# LCD_RGB.net
KiCad netlist of a schematic drawn in Altium Designer
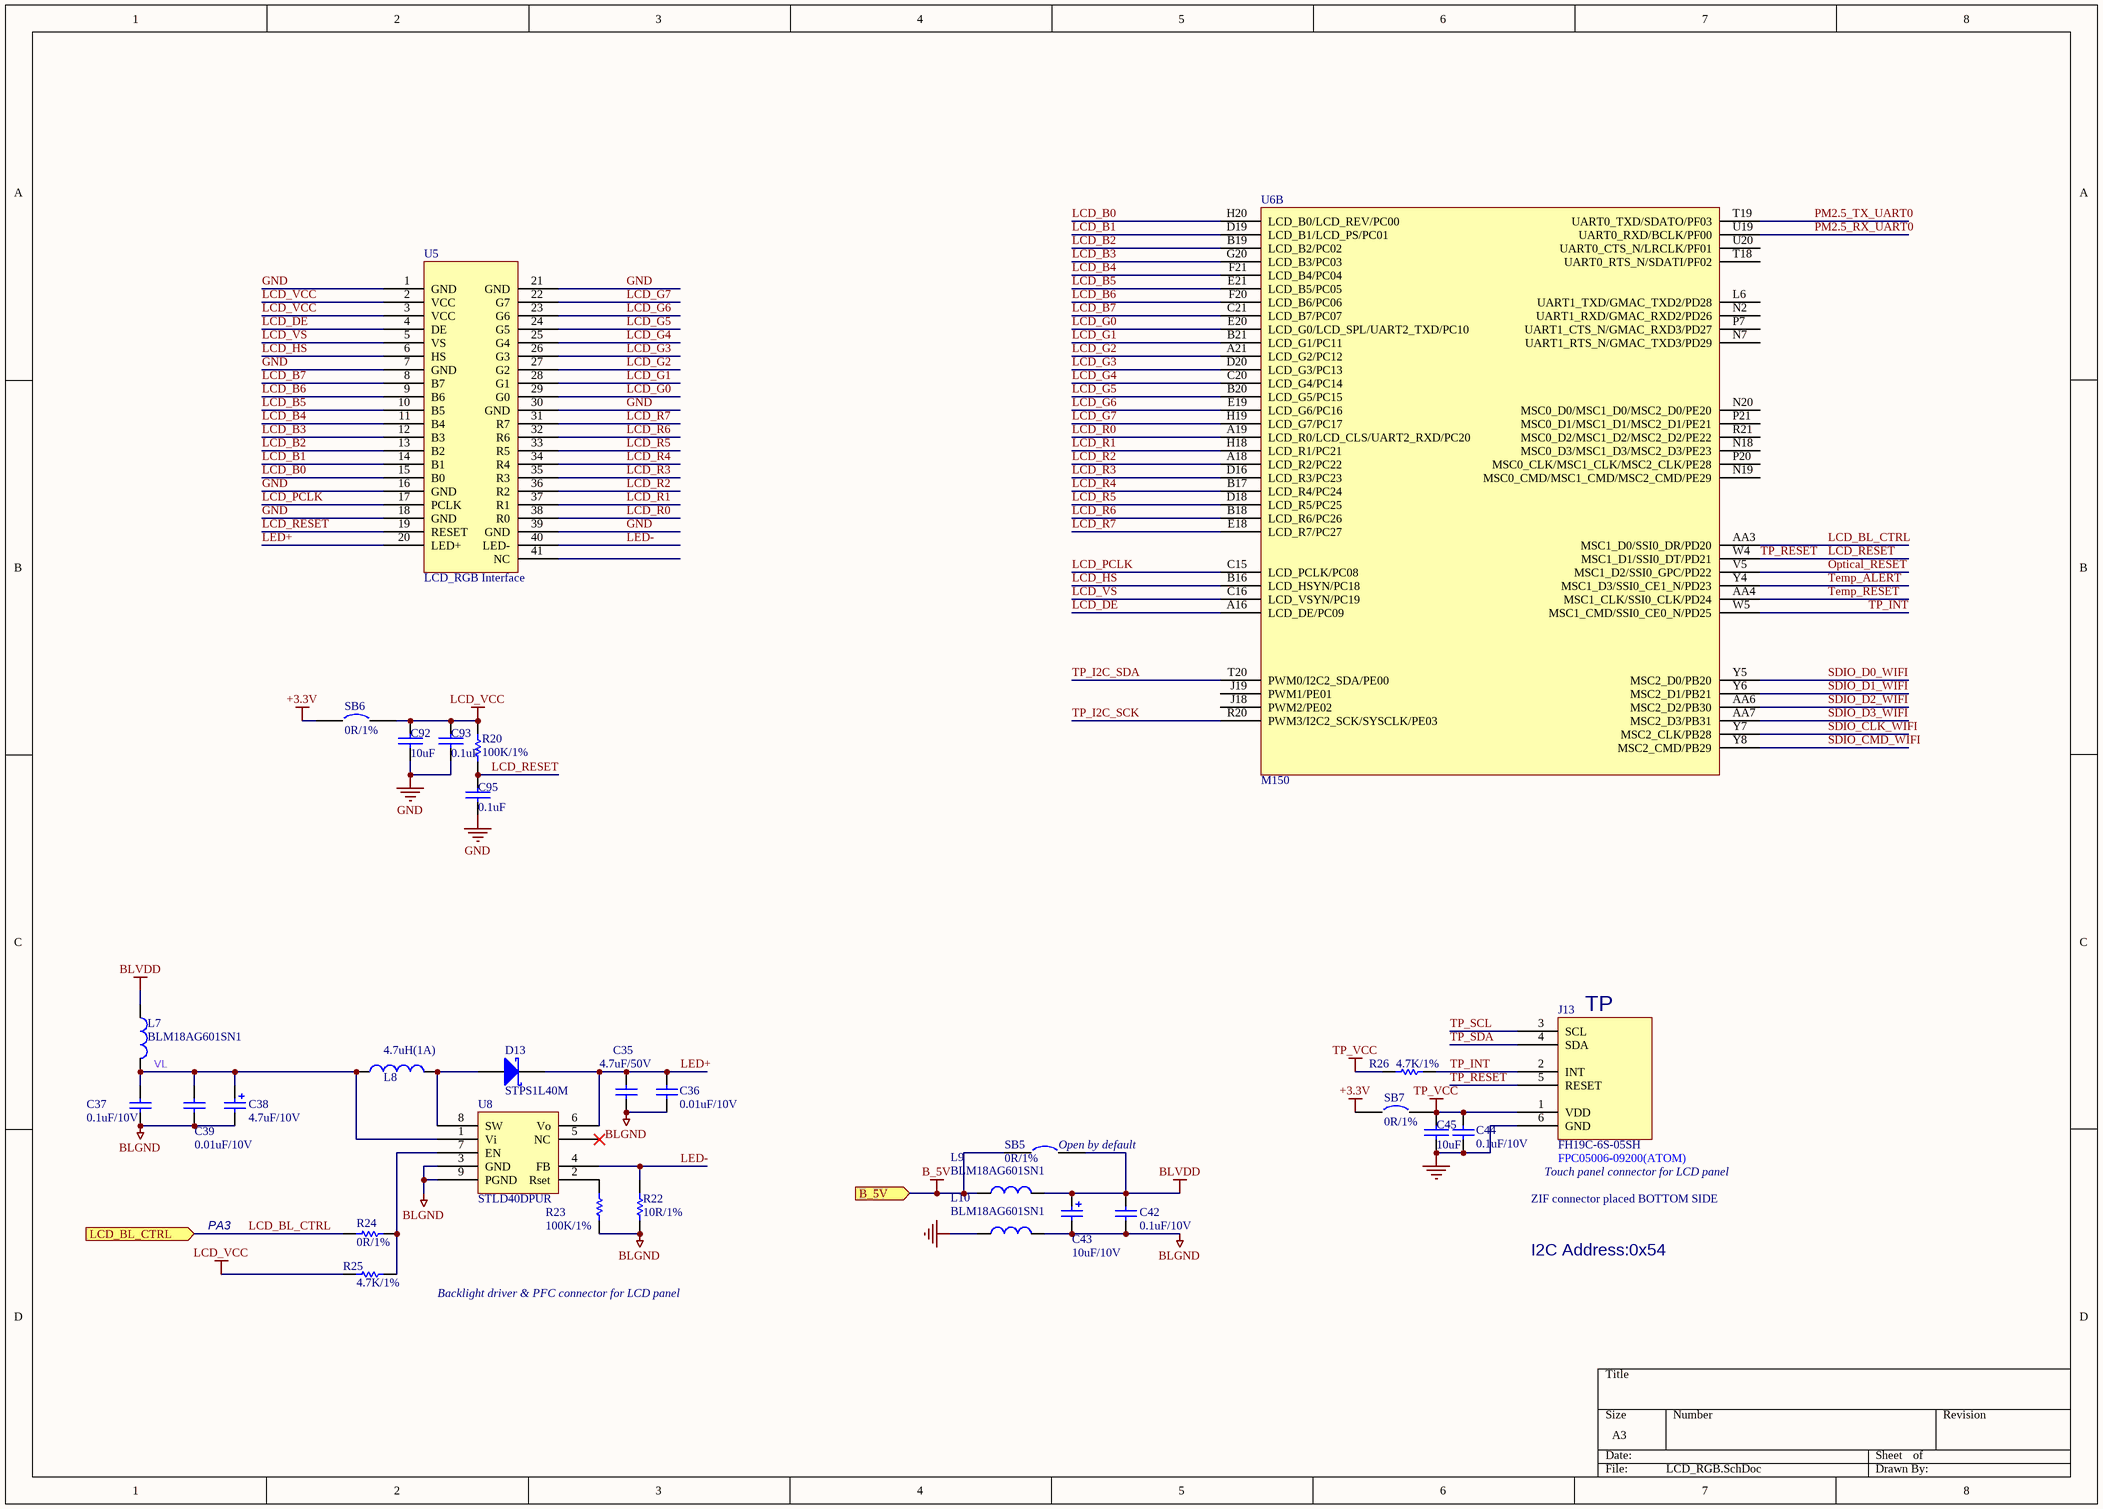
[diagram p0: LCD_RGB.SchDoc]

(export (version "E")
  (design (tool "Eeschema 10.0.6"))
  (components
    (comp (ref "C35")
      (value "4.7uF/50V")
      (footprint "0603C")
      (description "厂家：Murata，型号：")
      (fields (field (name "PUBLISHER") "Altium Limited"))
      (libsource (lib "Miscellaneous Devices") (part "CAP"))
    )
    (comp (ref "C36")
      (value "0.01uF/10V")
      (footprint "0402C")
      (description "厂家：Murata，型号：")
      (fields (field (name "PUBLISHER") "Altium Limited"))
      (libsource (lib "*") (part "CAP"))
    )
    (comp (ref "C37")
      (value "0.1uF/10V")
      (footprint "0402C")
      (description "Capacitor")
      (fields (field (name "PUBLISHER") "Altium Limited"))
      (libsource (lib "Miscellaneous Devices") (part "CAP"))
    )
    (comp (ref "C38")
      (value "4.7uF/10V")
      (footprint "1206")
      (fields (field (name "PUBLISHER") "Altium Limited"))
      (libsource (lib "Miscellaneous Devices") (part "Cap Pol1"))
    )
    (comp (ref "C39")
      (value "0.01uF/10V")
      (footprint "0402C")
      (description "厂家：Murata，型号：")
      (fields (field (name "PUBLISHER") "Altium Limited"))
      (libsource (lib "Miscellaneous Devices") (part "CAP"))
    )
    (comp (ref "C42")
      (value "0.1uF/10V")
      (footprint "0402C")
      (description "Capacitor")
      (fields (field (name "PUBLISHER") "Altium Limited"))
      (libsource (lib "Miscellaneous Devices") (part "Cap"))
    )
    (comp (ref "C43")
      (value "10uF/10V")
      (footprint "TAN-A")
      (description "Polarized Capacitor (Radial)")
      (fields (field (name "PUBLISHER") "Altium Limited"))
      (libsource (lib "Miscellaneous Devices") (part "Cap Pol1"))
    )
    (comp (ref "C44")
      (value "0.1uF/10V")
      (footprint "0402C")
      (description "Capacitor")
      (fields (field (name "PUBLISHER") "Altium Limited"))
      (libsource (lib "Miscellaneous Devices") (part "CAP"))
    )
    (comp (ref "C45")
      (value "10uF")
      (footprint "0402C")
      (description "厂家：Murata，型号：GRM1555C1H120JA01D")
      (libsource (lib "Amber") (part "CAP"))
    )
    (comp (ref "C92")
      (value "10uF")
      (footprint "0402C")
      (description "厂家：Murata，型号：GRM1555C1H120JA01D")
      (libsource (lib "Amber") (part "CAP"))
    )
    (comp (ref "C93")
      (value "0.1uF")
      (footprint "0402C")
      (description "厂家：Murata，型号：GRM1555C1H120JA01D")
      (libsource (lib "Amber") (part "CAP"))
    )
    (comp (ref "C95")
      (value "0.1uF")
      (footprint "0402C")
      (description "厂家：Murata，型号：GRM1555C1H120JA01D")
      (libsource (lib "Amber") (part "CAP"))
    )
    (comp (ref "D13")
      (value "STPS1L40M")
      (footprint "DO-216AA")
      (description "Schottky Diode")
      (fields (field (name "PUBLISHER") "Altium Limited"))
      (libsource (lib "Miscellaneous Devices") (part "D Schottky"))
    )
    (comp (ref "J13")
      (value "FH19C-6S-05SH")
      (footprint "FH19C-6S-0R5SH_FPC_CPT")
      (description "ZIF connector placed bottom side")
      (libsource (lib "MB1166") (part "FH19C-6S-05SH"))
    )
    (comp (ref "L7")
      (value "BLM18AG601SN1")
      (footprint "0603R")
      (description "厂家：MURATA，型号：BLM18AG601SN1")
      (libsource (lib "Amber") (part "CHOKE"))
    )
    (comp (ref "L8")
      (value "4.7uH(1A)")
      (footprint "1210L")
      (description "Inductor")
      (fields (field (name "PUBLISHER") "Altium Limited"))
      (libsource (lib "Miscellaneous Devices") (part "Inductor"))
    )
    (comp (ref "L9")
      (value "BLM18AG601SN1")
      (footprint "0603R")
      (description "厂家：MURATA，型号：BLM18AG601SN1")
      (libsource (lib "Amber") (part "CHOKE"))
    )
    (comp (ref "L10")
      (value "BLM18AG601SN1")
      (footprint "0603R")
      (description "厂家：MURATA，型号：BLM18AG601SN1")
      (libsource (lib "Amber") (part "CHOKE"))
    )
    (comp (ref "R20")
      (value "100K/1%")
      (footprint "0402R")
      (description "Resistor")
      (fields (field (name "PUBLISHER") "Altium Limited"))
      (libsource (lib "Miscellaneous Devices") (part "Res1"))
    )
    (comp (ref "R22")
      (value "10R/1%")
      (footprint "0603R")
      (description "Resistor")
      (fields (field (name "PUBLISHER") "Altium Limited"))
      (libsource (lib "Miscellaneous Devices") (part "Res1"))
    )
    (comp (ref "R23")
      (value "100K/1%")
      (footprint "0402R")
      (description "Resistor")
      (fields (field (name "PUBLISHER") "Altium Limited"))
      (libsource (lib "Miscellaneous Devices") (part "Res1"))
    )
    (comp (ref "R24")
      (value "0R/1%")
      (footprint "0603R")
      (description "Resistor")
      (fields (field (name "PUBLISHER") "Altium Limited"))
      (libsource (lib "Miscellaneous Devices") (part "Res1"))
    )
    (comp (ref "R25")
      (value "4.7K/1%")
      (footprint "0402R")
      (description "厂家：Yageo，型号：")
      (fields (field (name "PUBLISHER") "Altium Limited"))
      (libsource (lib "Miscellaneous Devices") (part "Res1"))
    )
    (comp (ref "R26")
      (value "4.7K/1%")
      (footprint "0402R")
      (description "厂家：Yageo，型号：")
      (fields (field (name "PUBLISHER") "Altium Limited"))
      (libsource (lib "*") (part "Res1"))
    )
    (comp (ref "SB5")
      (value "0R/1%")
      (footprint "SB_0603")
      (description "Circuit Breaker")
      (fields (field (name "PUBLISHER") "Altium Limited"))
      (libsource (lib "Miscellaneous Devices") (part "Circuit Breaker"))
    )
    (comp (ref "SB6")
      (value "0R/1%")
      (footprint "SB_0603")
      (description "Circuit Breaker")
      (fields (field (name "PUBLISHER") "Altium Limited"))
      (libsource (lib "Miscellaneous Devices") (part "Circuit Breaker"))
    )
    (comp (ref "SB7")
      (value "0R/1%")
      (footprint "SB_0603")
      (description "Circuit Breaker")
      (fields (field (name "PUBLISHER") "Altium Limited"))
      (libsource (lib "Miscellaneous Devices") (part "Circuit Breaker"))
    )
    (comp (ref "U5") (value "LCD_RGB Interface") (libsource (lib "M150") (part "LCD_RGB Interface")))
    (comp (ref "U6") (value "M150") (footprint "Model Name") (libsource (lib "M150") (part "M150")))
    (comp (ref "U8")
      (value "STLD40DPUR")
      (footprint "SON8_0R65_3X3")
      (libsource (lib "3.2LCD_daughterboard") (part "STLD40DPMR"))
    )
  )
  (nets
    (net (code "1") (name "+3.3V") (class "Default")
      (node (ref "SB6") (pin "1") (pinfunction "1_1") (pintype "passive"))
      (node (ref "SB7") (pin "1") (pinfunction "1_1") (pintype "passive"))
    )
    (net (code "2") (name "/LCD_B0") (class "Default")
      (node (ref "U5") (pin "15") (pinfunction "B0_15") (pintype "passive"))
      (node (ref "U6") (pin "H20") (pinfunction "LCD_B0/LCD_REV/PC00_H20") (pintype "passive"))
    )
    (net (code "3") (name "/LCD_B1") (class "Default")
      (node (ref "U5") (pin "14") (pinfunction "B1_14") (pintype "passive"))
      (node (ref "U6") (pin "D19") (pinfunction "LCD_B1/LCD_PS/PC01_D19") (pintype "passive"))
    )
    (net (code "4") (name "/LCD_B2") (class "Default")
      (node (ref "U5") (pin "13") (pinfunction "B2_13") (pintype "passive"))
      (node (ref "U6") (pin "B19") (pinfunction "LCD_B2/PC02_B19") (pintype "passive"))
    )
    (net (code "5") (name "/LCD_B3") (class "Default")
      (node (ref "U5") (pin "12") (pinfunction "B3_12") (pintype "passive"))
      (node (ref "U6") (pin "G20") (pinfunction "LCD_B3/PC03_G20") (pintype "passive"))
    )
    (net (code "6") (name "/LCD_B4") (class "Default")
      (node (ref "U5") (pin "11") (pinfunction "B4_11") (pintype "passive"))
      (node (ref "U6") (pin "F21") (pinfunction "LCD_B4/PC04_F21") (pintype "passive"))
    )
    (net (code "7") (name "/LCD_B5") (class "Default")
      (node (ref "U5") (pin "10") (pinfunction "B5_10") (pintype "passive"))
      (node (ref "U6") (pin "E21") (pinfunction "LCD_B5/PC05_E21") (pintype "passive"))
    )
    (net (code "8") (name "/LCD_B6") (class "Default")
      (node (ref "U5") (pin "9") (pinfunction "B6_9") (pintype "passive"))
      (node (ref "U6") (pin "F20") (pinfunction "LCD_B6/PC06_F20") (pintype "passive"))
    )
    (net (code "9") (name "/LCD_B7") (class "Default")
      (node (ref "U5") (pin "8") (pinfunction "B7_8") (pintype "passive"))
      (node (ref "U6") (pin "C21") (pinfunction "LCD_B7/PC07_C21") (pintype "passive"))
    )
    (net (code "10") (name "/LCD_BL_CTRL") (class "Default")
      (node (ref "R24") (pin "2") (pinfunction "2_2") (pintype "passive"))
      (node (ref "U6") (pin "AA3") (pinfunction "MSC1_D0/SSI0_DR/PD20_AA3") (pintype "passive"))
    )
    (net (code "11") (name "/LCD_DE") (class "Default")
      (node (ref "U5") (pin "4") (pinfunction "DE_4") (pintype "passive"))
      (node (ref "U6") (pin "A16") (pinfunction "LCD_DE/PC09_A16") (pintype "passive"))
    )
    (net (code "12") (name "/LCD_G0") (class "Default")
      (node (ref "U5") (pin "29") (pinfunction "G0_29") (pintype "passive"))
      (node (ref "U6") (pin "E20") (pinfunction "LCD_G0/LCD_SPL/UART2_TXD/PC10_E20") (pintype "passive"))
    )
    (net (code "13") (name "/LCD_G1") (class "Default")
      (node (ref "U5") (pin "28") (pinfunction "G1_28") (pintype "passive"))
      (node (ref "U6") (pin "B21") (pinfunction "LCD_G1/PC11_B21") (pintype "passive"))
    )
    (net (code "14") (name "/LCD_G2") (class "Default")
      (node (ref "U5") (pin "27") (pinfunction "G2_27") (pintype "passive"))
      (node (ref "U6") (pin "A21") (pinfunction "LCD_G2/PC12_A21") (pintype "passive"))
    )
    (net (code "15") (name "/LCD_G3") (class "Default")
      (node (ref "U5") (pin "26") (pinfunction "G3_26") (pintype "passive"))
      (node (ref "U6") (pin "D20") (pinfunction "LCD_G3/PC13_D20") (pintype "passive"))
    )
    (net (code "16") (name "/LCD_G4") (class "Default")
      (node (ref "U5") (pin "25") (pinfunction "G4_25") (pintype "passive"))
      (node (ref "U6") (pin "C20") (pinfunction "LCD_G4/PC14_C20") (pintype "passive"))
    )
    (net (code "17") (name "/LCD_G5") (class "Default")
      (node (ref "U5") (pin "24") (pinfunction "G5_24") (pintype "passive"))
      (node (ref "U6") (pin "B20") (pinfunction "LCD_G5/PC15_B20") (pintype "passive"))
    )
    (net (code "18") (name "/LCD_G6") (class "Default")
      (node (ref "U5") (pin "23") (pinfunction "G6_23") (pintype "passive"))
      (node (ref "U6") (pin "E19") (pinfunction "LCD_G6/PC16_E19") (pintype "passive"))
    )
    (net (code "19") (name "/LCD_G7") (class "Default")
      (node (ref "U5") (pin "22") (pinfunction "G7_22") (pintype "passive"))
      (node (ref "U6") (pin "H19") (pinfunction "LCD_G7/PC17_H19") (pintype "passive"))
    )
    (net (code "20") (name "/LCD_HS") (class "Default")
      (node (ref "U5") (pin "6") (pinfunction "HS_6") (pintype "passive"))
      (node (ref "U6") (pin "B16") (pinfunction "LCD_HSYN/PC18_B16") (pintype "passive"))
    )
    (net (code "21") (name "/LCD_PCLK") (class "Default")
      (node (ref "U5") (pin "17") (pinfunction "PCLK_17") (pintype "passive"))
      (node (ref "U6") (pin "C15") (pinfunction "LCD_PCLK/PC08_C15") (pintype "passive"))
    )
    (net (code "22") (name "/LCD_R0") (class "Default")
      (node (ref "U5") (pin "38") (pinfunction "R0_38") (pintype "passive"))
      (node (ref "U6") (pin "A19") (pinfunction "LCD_R0/LCD_CLS/UART2_RXD/PC20_A19") (pintype "passive"))
    )
    (net (code "23") (name "/LCD_R1") (class "Default")
      (node (ref "U5") (pin "37") (pinfunction "R1_37") (pintype "passive"))
      (node (ref "U6") (pin "H18") (pinfunction "LCD_R1/PC21_H18") (pintype "passive"))
    )
    (net (code "24") (name "/LCD_R2") (class "Default")
      (node (ref "U5") (pin "36") (pinfunction "R2_36") (pintype "passive"))
      (node (ref "U6") (pin "A18") (pinfunction "LCD_R2/PC22_A18") (pintype "passive"))
    )
    (net (code "25") (name "/LCD_R3") (class "Default")
      (node (ref "U5") (pin "35") (pinfunction "R3_35") (pintype "passive"))
      (node (ref "U6") (pin "D16") (pinfunction "LCD_R3/PC23_D16") (pintype "passive"))
    )
    (net (code "26") (name "/LCD_R4") (class "Default")
      (node (ref "U5") (pin "34") (pinfunction "R4_34") (pintype "passive"))
      (node (ref "U6") (pin "B17") (pinfunction "LCD_R4/PC24_B17") (pintype "passive"))
    )
    (net (code "27") (name "/LCD_R5") (class "Default")
      (node (ref "U5") (pin "33") (pinfunction "R5_33") (pintype "passive"))
      (node (ref "U6") (pin "D18") (pinfunction "LCD_R5/PC25_D18") (pintype "passive"))
    )
    (net (code "28") (name "/LCD_R6") (class "Default")
      (node (ref "U5") (pin "32") (pinfunction "R6_32") (pintype "passive"))
      (node (ref "U6") (pin "B18") (pinfunction "LCD_R6/PC26_B18") (pintype "passive"))
    )
    (net (code "29") (name "/LCD_R7") (class "Default")
      (node (ref "U5") (pin "31") (pinfunction "R7_31") (pintype "passive"))
      (node (ref "U6") (pin "E18") (pinfunction "LCD_R7/PC27_E18") (pintype "passive"))
    )
    (net (code "30") (name "/LCD_RESET") (class "Default")
      (node (ref "C95") (pin "2") (pinfunction "2_2") (pintype "passive"))
      (node (ref "J13") (pin "5") (pinfunction "RESET_5") (pintype "passive"))
      (node (ref "R20") (pin "2") (pinfunction "2_2") (pintype "passive"))
      (node (ref "U5") (pin "19") (pinfunction "RESET_19") (pintype "passive"))
      (node (ref "U6") (pin "W4") (pinfunction "MSC1_D1/SSI0_DT/PD21_W4") (pintype "passive"))
    )
    (net (code "31") (name "/LCD_VS") (class "Default")
      (node (ref "U5") (pin "5") (pinfunction "VS_5") (pintype "passive"))
      (node (ref "U6") (pin "C16") (pinfunction "LCD_VSYN/PC19_C16") (pintype "passive"))
    )
    (net (code "32") (name "/LED+") (class "Default")
      (node (ref "C35") (pin "1") (pinfunction "1_1") (pintype "passive"))
      (node (ref "C36") (pin "2") (pinfunction "2_2") (pintype "passive"))
      (node (ref "D13") (pin "2") (pinfunction "K_2") (pintype "passive"))
      (node (ref "U5") (pin "20") (pinfunction "LED+_20") (pintype "passive"))
      (node (ref "U8") (pin "6") (pinfunction "Vo_6") (pintype "passive"))
    )
    (net (code "33") (name "/LED-") (class "Default")
      (node (ref "R22") (pin "2") (pinfunction "2_2") (pintype "passive"))
      (node (ref "U5") (pin "40") (pinfunction "LED-_40") (pintype "passive"))
      (node (ref "U8") (pin "4") (pinfunction "FB_4") (pintype "passive"))
    )
    (net (code "34") (name "/Optical_RESET") (class "Default")
      (node (ref "U6") (pin "V5") (pinfunction "MSC1_D2/SSI0_GPC/PD22_V5") (pintype "passive"))
    )
    (net (code "35") (name "/PM2.5_RX_UART0") (class "Default")
      (node (ref "U6") (pin "U19") (pinfunction "UART0_RXD/BCLK/PF00_U19") (pintype "passive"))
    )
    (net (code "36") (name "/PM2.5_TX_UART0") (class "Default")
      (node (ref "U6") (pin "T19") (pinfunction "UART0_TXD/SDATO/PF03_T19") (pintype "passive"))
    )
    (net (code "37") (name "/SDIO_CLK_WIFI") (class "Default")
      (node (ref "U6") (pin "Y7") (pinfunction "MSC2_CLK/PB28_Y7") (pintype "passive"))
    )
    (net (code "38") (name "/SDIO_CMD_WIFI") (class "Default")
      (node (ref "U6") (pin "Y8") (pinfunction "MSC2_CMD/PB29_Y8") (pintype "passive"))
    )
    (net (code "39") (name "/SDIO_D0_WIFI") (class "Default")
      (node (ref "U6") (pin "Y5") (pinfunction "MSC2_D0/PB20_Y5") (pintype "passive"))
    )
    (net (code "40") (name "/SDIO_D1_WIFI") (class "Default")
      (node (ref "U6") (pin "Y6") (pinfunction "MSC2_D1/PB21_Y6") (pintype "passive"))
    )
    (net (code "41") (name "/SDIO_D2_WIFI") (class "Default")
      (node (ref "U6") (pin "AA6") (pinfunction "MSC2_D2/PB30_AA6") (pintype "passive"))
    )
    (net (code "42") (name "/SDIO_D3_WIFI") (class "Default")
      (node (ref "U6") (pin "AA7") (pinfunction "MSC2_D3/PB31_AA7") (pintype "passive"))
    )
    (net (code "43") (name "/TP_I2C_SCK") (class "Default")
      (node (ref "U6") (pin "R20") (pinfunction "PWM3/I2C2_SCK/SYSCLK/PE03_R20") (pintype "passive"))
    )
    (net (code "44") (name "/TP_I2C_SDA") (class "Default")
      (node (ref "U6") (pin "T20") (pinfunction "PWM0/I2C2_SDA/PE00_T20") (pintype "passive"))
    )
    (net (code "45") (name "/TP_INT") (class "Default")
      (node (ref "J13") (pin "2") (pinfunction "INT_2") (pintype "passive"))
      (node (ref "R26") (pin "2") (pinfunction "2_2") (pintype "passive"))
      (node (ref "U6") (pin "W5") (pinfunction "MSC1_CMD/SSI0_CE0_N/PD25_W5") (pintype "passive"))
    )
    (net (code "46") (name "/TP_SCL") (class "Default")
      (node (ref "J13") (pin "3") (pinfunction "SCL_3") (pintype "passive"))
    )
    (net (code "47") (name "/TP_SDA") (class "Default")
      (node (ref "J13") (pin "4") (pinfunction "SDA_4") (pintype "passive"))
    )
    (net (code "48") (name "/Temp_ALERT") (class "Default")
      (node (ref "U6") (pin "Y4") (pinfunction "MSC1_D3/SSI0_CE1_N/PD23_Y4") (pintype "passive"))
    )
    (net (code "49") (name "/Temp_RESET") (class "Default")
      (node (ref "U6") (pin "AA4") (pinfunction "MSC1_CLK/SSI0_CLK/PD24_AA4") (pintype "passive"))
    )
    (net (code "50") (name "/VL") (class "Default")
      (node (ref "C37") (pin "2") (pinfunction "2_2") (pintype "passive"))
      (node (ref "C38") (pin "1") (pinfunction "1_1") (pintype "passive"))
      (node (ref "C39") (pin "2") (pinfunction "2_2") (pintype "passive"))
      (node (ref "L7") (pin "2") (pinfunction "2_2") (pintype "passive"))
      (node (ref "L8") (pin "1") (pinfunction "1_1") (pintype "passive"))
      (node (ref "U8") (pin "1") (pinfunction "Vi_1") (pintype "passive"))
    )
    (net (code "51") (name "BLGND") (class "Default")
      (node (ref "C35") (pin "2") (pinfunction "2_2") (pintype "passive"))
      (node (ref "C36") (pin "1") (pinfunction "1_1") (pintype "passive"))
      (node (ref "C37") (pin "1") (pinfunction "1_1") (pintype "passive"))
      (node (ref "C38") (pin "2") (pinfunction "2_2") (pintype "passive"))
      (node (ref "C39") (pin "1") (pinfunction "1_1") (pintype "passive"))
      (node (ref "C42") (pin "2") (pinfunction "2_2") (pintype "passive"))
      (node (ref "C43") (pin "2") (pinfunction "2_2") (pintype "passive"))
      (node (ref "L10") (pin "2") (pinfunction "2_2") (pintype "passive"))
      (node (ref "R22") (pin "1") (pinfunction "1_1") (pintype "passive"))
      (node (ref "R23") (pin "2") (pinfunction "2_2") (pintype "passive"))
      (node (ref "U8") (pin "3") (pinfunction "GND_3") (pintype "passive"))
      (node (ref "U8") (pin "9") (pinfunction "PGND_9") (pintype "passive"))
    )
    (net (code "52") (name "BLVDD") (class "Default")
      (node (ref "C42") (pin "1") (pinfunction "1_1") (pintype "passive"))
      (node (ref "C43") (pin "1") (pinfunction "1_1") (pintype "passive"))
      (node (ref "L7") (pin "1") (pinfunction "1_1") (pintype "passive"))
      (node (ref "L9") (pin "2") (pinfunction "2_2") (pintype "passive"))
      (node (ref "SB5") (pin "2") (pinfunction "2_2") (pintype "passive"))
    )
    (net (code "53") (name "B_5V") (class "Default")
      (node (ref "L9") (pin "1") (pinfunction "1_1") (pintype "passive"))
      (node (ref "SB5") (pin "1") (pinfunction "1_1") (pintype "passive"))
    )
    (net (code "54") (name "GND") (class "Default")
      (node (ref "C44") (pin "1") (pinfunction "1_1") (pintype "passive"))
      (node (ref "C45") (pin "1") (pinfunction "1_1") (pintype "passive"))
      (node (ref "C92") (pin "1") (pinfunction "1_1") (pintype "passive"))
      (node (ref "C93") (pin "1") (pinfunction "1_1") (pintype "passive"))
      (node (ref "C95") (pin "1") (pinfunction "1_1") (pintype "passive"))
      (node (ref "J13") (pin "6") (pinfunction "GND_6") (pintype "passive"))
      (node (ref "L10") (pin "1") (pinfunction "1_1") (pintype "passive"))
      (node (ref "U5") (pin "1") (pinfunction "GND_1") (pintype "passive"))
      (node (ref "U5") (pin "16") (pinfunction "GND_16") (pintype "passive"))
      (node (ref "U5") (pin "18") (pinfunction "GND_18") (pintype "passive"))
      (node (ref "U5") (pin "21") (pinfunction "GND_21") (pintype "passive"))
      (node (ref "U5") (pin "30") (pinfunction "GND_30") (pintype "passive"))
      (node (ref "U5") (pin "39") (pinfunction "GND_39") (pintype "passive"))
      (node (ref "U5") (pin "7") (pinfunction "GND_7") (pintype "passive"))
    )
    (net (code "55") (name "LCD_VCC") (class "Default")
      (node (ref "C92") (pin "2") (pinfunction "2_2") (pintype "passive"))
      (node (ref "C93") (pin "2") (pinfunction "2_2") (pintype "passive"))
      (node (ref "R20") (pin "1") (pinfunction "1_1") (pintype "passive"))
      (node (ref "R25") (pin "2") (pinfunction "2_2") (pintype "passive"))
      (node (ref "SB6") (pin "2") (pinfunction "2_2") (pintype "passive"))
      (node (ref "U5") (pin "2") (pinfunction "VCC_2") (pintype "passive"))
      (node (ref "U5") (pin "3") (pinfunction "VCC_3") (pintype "passive"))
    )
    (net (code "56") (name "Net-(D13-A)") (class "Default")
      (node (ref "D13") (pin "1") (pinfunction "A_1") (pintype "passive"))
      (node (ref "L8") (pin "2") (pinfunction "2_2") (pintype "passive"))
      (node (ref "U8") (pin "8") (pinfunction "SW_8") (pintype "passive"))
    )
    (net (code "57") (name "Net-(U8-EN)") (class "Default")
      (node (ref "R24") (pin "1") (pinfunction "1_1") (pintype "passive"))
      (node (ref "R25") (pin "1") (pinfunction "1_1") (pintype "passive"))
      (node (ref "U8") (pin "7") (pinfunction "EN_7") (pintype "passive"))
    )
    (net (code "58") (name "Net-(U8-Rset)") (class "Default")
      (node (ref "R23") (pin "1") (pinfunction "1_1") (pintype "passive"))
      (node (ref "U8") (pin "2") (pinfunction "Rset_2") (pintype "passive"))
    )
    (net (code "59") (name "TP_VCC") (class "Default")
      (node (ref "C44") (pin "2") (pinfunction "2_2") (pintype "passive"))
      (node (ref "C45") (pin "2") (pinfunction "2_2") (pintype "passive"))
      (node (ref "J13") (pin "1") (pinfunction "VDD_1") (pintype "passive"))
      (node (ref "R26") (pin "1") (pinfunction "1_1") (pintype "passive"))
      (node (ref "SB7") (pin "2") (pinfunction "2_2") (pintype "passive"))
    )
    (net (code "60") (name "unconnected-(U5-NC-Pad41)") (class "Default")
      (node (ref "U5") (pin "41") (pinfunction "NC_41") (pintype "passive"))
    )
    (net (code "61") (name "unconnected-(U6B-MSC0_CLK{slash}MSC1_CLK{slash}MSC2_CLK{slash}PE28-PadP20)") (class "Default")
      (node (ref "U6") (pin "P20") (pinfunction "MSC0_CLK/MSC1_CLK/MSC2_CLK/PE28_P20") (pintype "passive"))
    )
    (net (code "62") (name "unconnected-(U6B-MSC0_CMD{slash}MSC1_CMD{slash}MSC2_CMD{slash}PE29-PadN19)") (class "Default")
      (node (ref "U6") (pin "N19") (pinfunction "MSC0_CMD/MSC1_CMD/MSC2_CMD/PE29_N19") (pintype "passive"))
    )
    (net (code "63") (name "unconnected-(U6B-MSC0_D0{slash}MSC1_D0{slash}MSC2_D0{slash}PE20-PadN20)") (class "Default")
      (node (ref "U6") (pin "N20") (pinfunction "MSC0_D0/MSC1_D0/MSC2_D0/PE20_N20") (pintype "passive"))
    )
    (net (code "64") (name "unconnected-(U6B-MSC0_D1{slash}MSC1_D1{slash}MSC2_D1{slash}PE21-PadP21)") (class "Default")
      (node (ref "U6") (pin "P21") (pinfunction "MSC0_D1/MSC1_D1/MSC2_D1/PE21_P21") (pintype "passive"))
    )
    (net (code "65") (name "unconnected-(U6B-MSC0_D2{slash}MSC1_D2{slash}MSC2_D2{slash}PE22-PadR21)") (class "Default")
      (node (ref "U6") (pin "R21") (pinfunction "MSC0_D2/MSC1_D2/MSC2_D2/PE22_R21") (pintype "passive"))
    )
    (net (code "66") (name "unconnected-(U6B-MSC0_D3{slash}MSC1_D3{slash}MSC2_D3{slash}PE23-PadN18)") (class "Default")
      (node (ref "U6") (pin "N18") (pinfunction "MSC0_D3/MSC1_D3/MSC2_D3/PE23_N18") (pintype "passive"))
    )
    (net (code "67") (name "unconnected-(U6B-PWM1{slash}PE01-PadJ19)") (class "Default")
      (node (ref "U6") (pin "J19") (pinfunction "PWM1/PE01_J19") (pintype "passive"))
    )
    (net (code "68") (name "unconnected-(U6B-PWM2{slash}PE02-PadJ18)") (class "Default")
      (node (ref "U6") (pin "J18") (pinfunction "PWM2/PE02_J18") (pintype "passive"))
    )
    (net (code "69") (name "unconnected-(U6B-UART0_CTS_N{slash}LRCLK{slash}PF01-PadU20)") (class "Default")
      (node (ref "U6") (pin "U20") (pinfunction "UART0_CTS_N/LRCLK/PF01_U20") (pintype "passive"))
    )
    (net (code "70") (name "unconnected-(U6B-UART0_RTS_N{slash}SDATI{slash}PF02-PadT18)") (class "Default")
      (node (ref "U6") (pin "T18") (pinfunction "UART0_RTS_N/SDATI/PF02_T18") (pintype "passive"))
    )
    (net (code "71") (name "unconnected-(U6B-UART1_CTS_N{slash}GMAC_RXD3{slash}PD27-PadP7)") (class "Default")
      (node (ref "U6") (pin "P7") (pinfunction "UART1_CTS_N/GMAC_RXD3/PD27_P7") (pintype "passive"))
    )
    (net (code "72") (name "unconnected-(U6B-UART1_RTS_N{slash}GMAC_TXD3{slash}PD29-PadN7)") (class "Default")
      (node (ref "U6") (pin "N7") (pinfunction "UART1_RTS_N/GMAC_TXD3/PD29_N7") (pintype "passive"))
    )
    (net (code "73") (name "unconnected-(U6B-UART1_RXD{slash}GMAC_RXD2{slash}PD26-PadN2)") (class "Default")
      (node (ref "U6") (pin "N2") (pinfunction "UART1_RXD/GMAC_RXD2/PD26_N2") (pintype "passive"))
    )
    (net (code "74") (name "unconnected-(U6B-UART1_TXD{slash}GMAC_TXD2{slash}PD28-PadL6)") (class "Default")
      (node (ref "U6") (pin "L6") (pinfunction "UART1_TXD/GMAC_TXD2/PD28_L6") (pintype "passive"))
    )
    (net (code "75") (name "unconnected-(U8-NC-Pad5)") (class "Default")
      (node (ref "U8") (pin "5") (pinfunction "NC_5") (pintype "passive+no_connect"))
    )
  )
)
